# RPI-CM3.net
KiCad netlist of a schematic drawn in Altium Designer
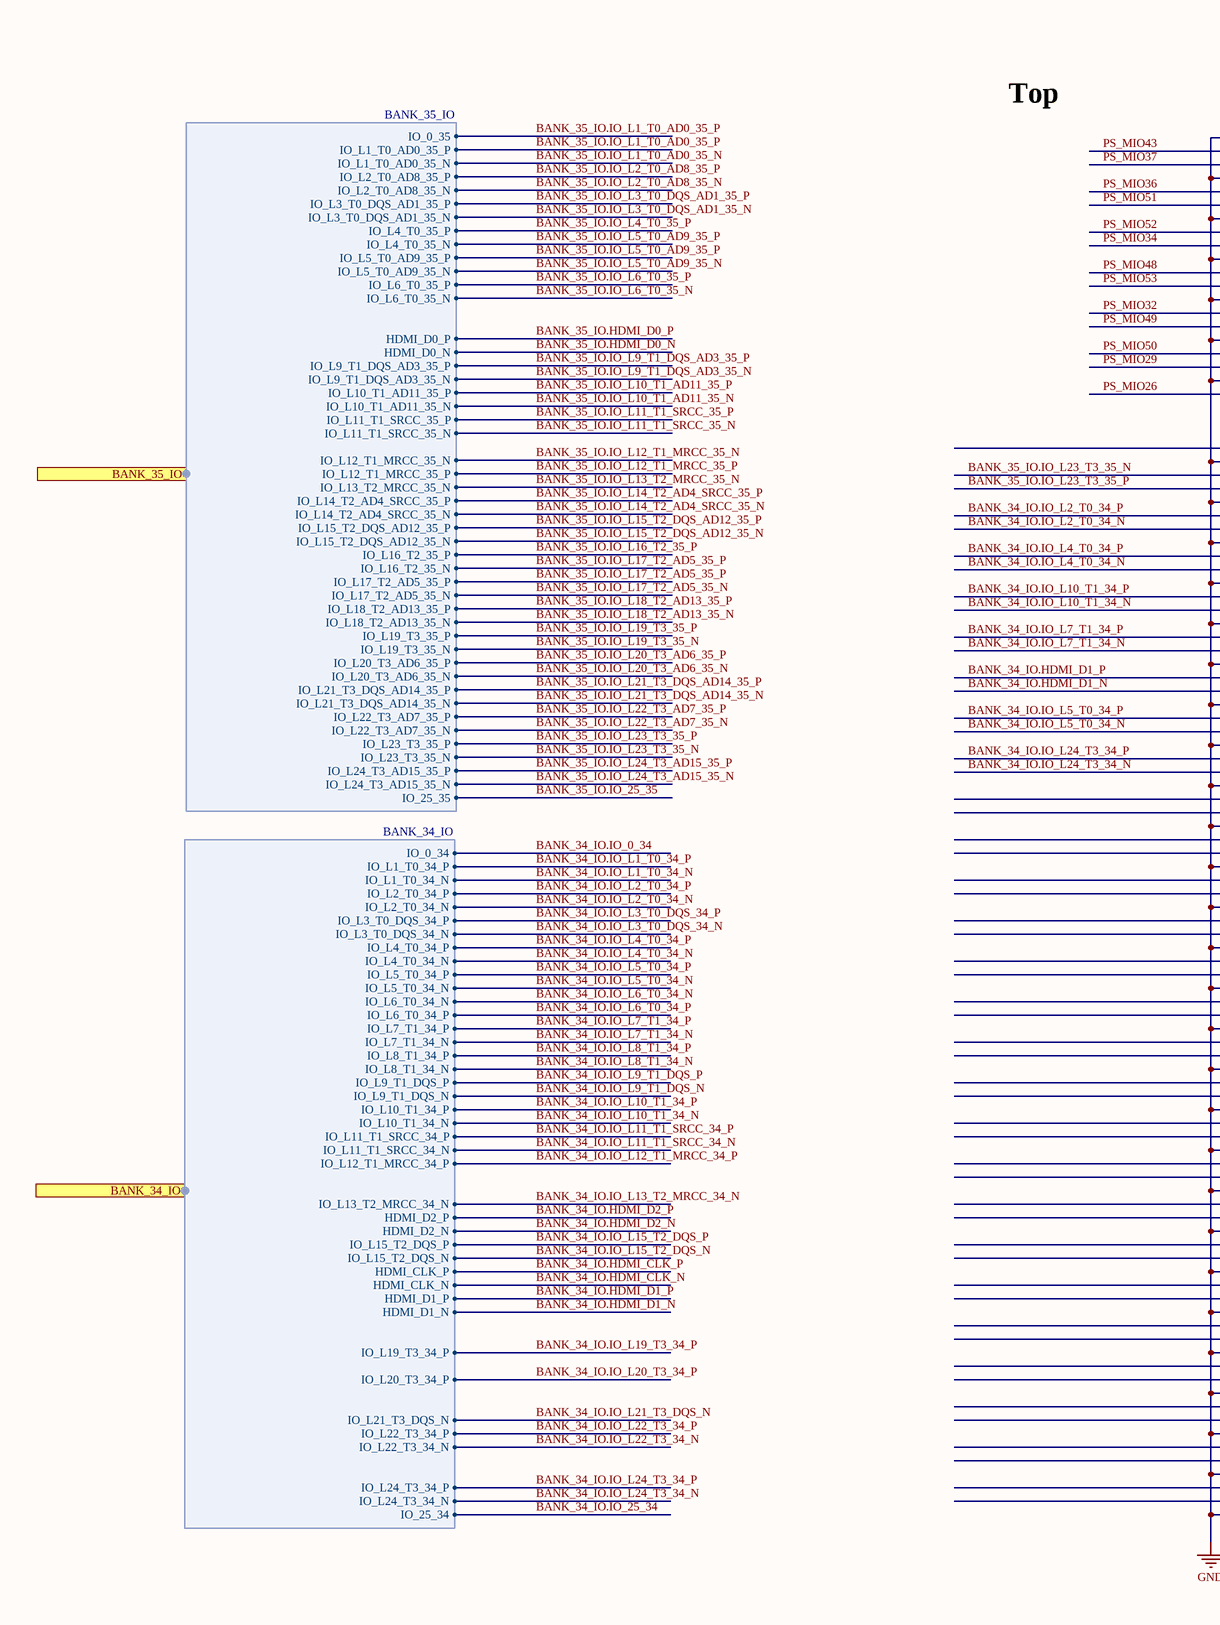
[diagram p0: RPI-CM3.SchDoc, left]
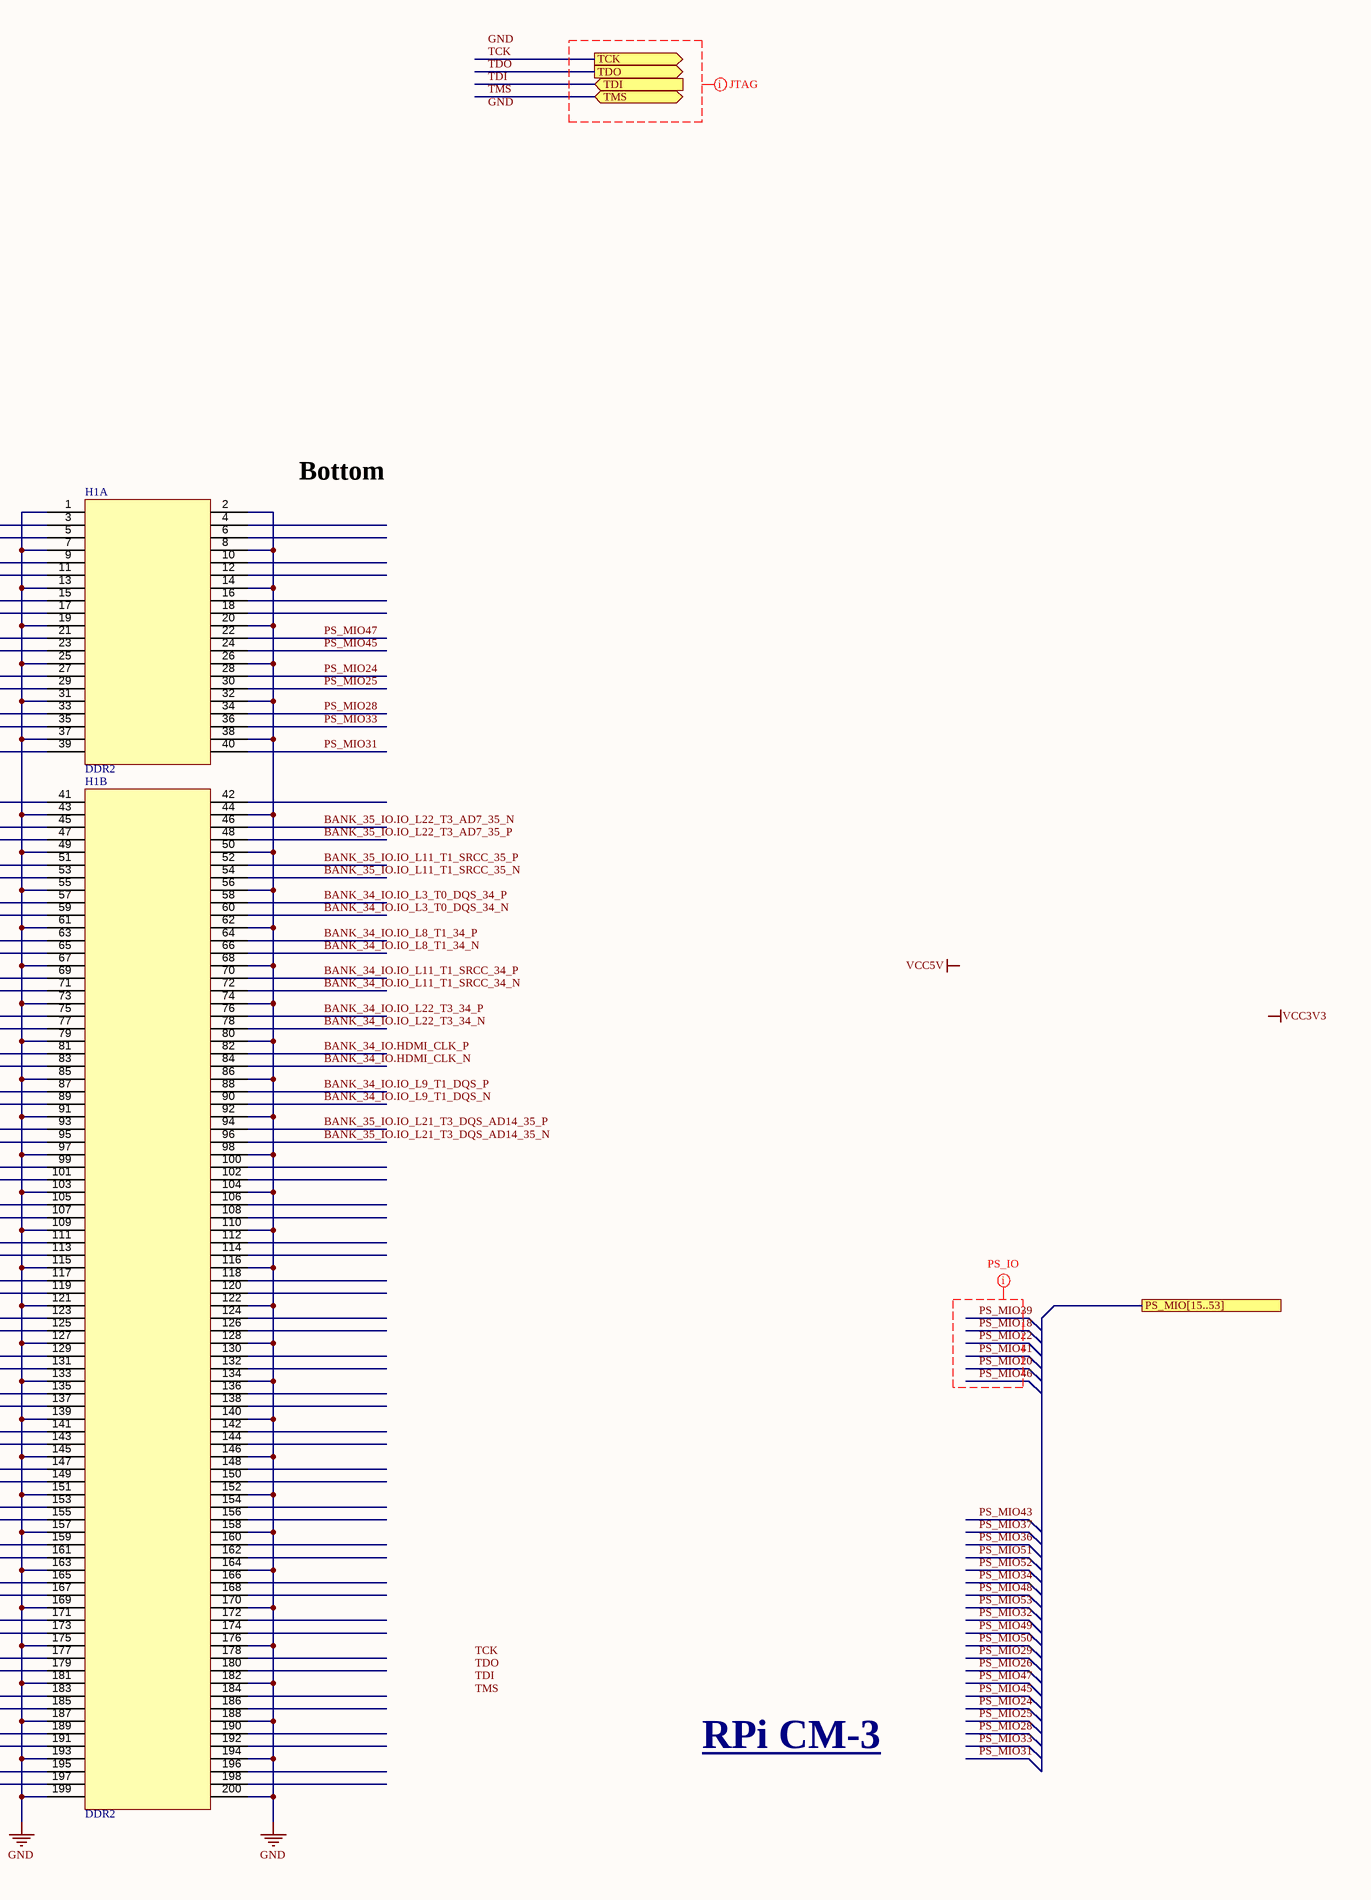
[diagram p1: RPI-CM3.SchDoc, right]

(export (version "E")
  (design (tool "Eeschema 10.0.6"))
  (components
    (comp (ref "H1")
      (value "DDR2")
      (footprint "DDR2-SO-DIMM")
      (libsource (lib "CCZynq") (part "DDR2_SODIMM"))
    )
  )
  (nets
    (net (code "16") (name "/BANK_34_IO.HDMI_CLK_N") (class "Default")
      (node (ref "H1") (pin "84") (pintype "passive"))
    )
    (net (code "17") (name "/BANK_34_IO.HDMI_CLK_P") (class "Default")
      (node (ref "H1") (pin "82") (pintype "passive"))
    )
    (net (code "18") (name "/BANK_34_IO.HDMI_D1_N") (class "Default")
      (node (ref "H1") (pin "77") (pintype "passive"))
    )
    (net (code "19") (name "/BANK_34_IO.HDMI_D1_P") (class "Default")
      (node (ref "H1") (pin "75") (pintype "passive"))
    )
    (net (code "26") (name "/BANK_34_IO.IO_L2_T0_34_N") (class "Default")
      (node (ref "H1") (pin "53") (pintype "passive"))
    )
    (net (code "27") (name "/BANK_34_IO.IO_L2_T0_34_P") (class "Default")
      (node (ref "H1") (pin "51") (pintype "passive"))
    )
    (net (code "28") (name "/BANK_34_IO.IO_L3_T0_DQS_34_N") (class "Default")
      (node (ref "H1") (pin "60") (pintype "passive"))
    )
    (net (code "29") (name "/BANK_34_IO.IO_L3_T0_DQS_34_P") (class "Default")
      (node (ref "H1") (pin "58") (pintype "passive"))
    )
    (net (code "30") (name "/BANK_34_IO.IO_L4_T0_34_N") (class "Default")
      (node (ref "H1") (pin "59") (pintype "passive"))
    )
    (net (code "31") (name "/BANK_34_IO.IO_L4_T0_34_P") (class "Default")
      (node (ref "H1") (pin "57") (pintype "passive"))
    )
    (net (code "32") (name "/BANK_34_IO.IO_L5_T0_34_N") (class "Default")
      (node (ref "H1") (pin "83") (pintype "passive"))
    )
    (net (code "33") (name "/BANK_34_IO.IO_L5_T0_34_P") (class "Default")
      (node (ref "H1") (pin "81") (pintype "passive"))
    )
    (net (code "36") (name "/BANK_34_IO.IO_L7_T1_34_N") (class "Default")
      (node (ref "H1") (pin "71") (pintype "passive"))
    )
    (net (code "37") (name "/BANK_34_IO.IO_L7_T1_34_P") (class "Default")
      (node (ref "H1") (pin "69") (pintype "passive"))
    )
    (net (code "38") (name "/BANK_34_IO.IO_L8_T1_34_N") (class "Default")
      (node (ref "H1") (pin "66") (pintype "passive"))
    )
    (net (code "39") (name "/BANK_34_IO.IO_L8_T1_34_P") (class "Default")
      (node (ref "H1") (pin "64") (pintype "passive"))
    )
    (net (code "40") (name "/BANK_34_IO.IO_L9_T1_DQS_N") (class "Default")
      (node (ref "H1") (pin "90") (pintype "passive"))
    )
    (net (code "41") (name "/BANK_34_IO.IO_L9_T1_DQS_P") (class "Default")
      (node (ref "H1") (pin "88") (pintype "passive"))
    )
    (net (code "42") (name "/BANK_34_IO.IO_L10_T1_34_N") (class "Default")
      (node (ref "H1") (pin "65") (pintype "passive"))
    )
    (net (code "43") (name "/BANK_34_IO.IO_L10_T1_34_P") (class "Default")
      (node (ref "H1") (pin "63") (pintype "passive"))
    )
    (net (code "44") (name "/BANK_34_IO.IO_L11_T1_SRCC_34_N") (class "Default")
      (node (ref "H1") (pin "72") (pintype "passive"))
    )
    (net (code "45") (name "/BANK_34_IO.IO_L11_T1_SRCC_34_P") (class "Default")
      (node (ref "H1") (pin "70") (pintype "passive"))
    )
    (net (code "53") (name "/BANK_34_IO.IO_L22_T3_34_N") (class "Default")
      (node (ref "H1") (pin "78") (pintype "passive"))
    )
    (net (code "54") (name "/BANK_34_IO.IO_L22_T3_34_P") (class "Default")
      (node (ref "H1") (pin "76") (pintype "passive"))
    )
    (net (code "55") (name "/BANK_34_IO.IO_L24_T3_34_N") (class "Default")
      (node (ref "H1") (pin "89") (pintype "passive"))
    )
    (net (code "56") (name "/BANK_34_IO.IO_L24_T3_34_P") (class "Default")
      (node (ref "H1") (pin "87") (pintype "passive"))
    )
    (net (code "75") (name "/BANK_35_IO.IO_L11_T1_SRCC_35_N") (class "Default")
      (node (ref "H1") (pin "54") (pintype "passive"))
    )
    (net (code "76") (name "/BANK_35_IO.IO_L11_T1_SRCC_35_P") (class "Default")
      (node (ref "H1") (pin "52") (pintype "passive"))
    )
    (net (code "93") (name "/BANK_35_IO.IO_L21_T3_DQS_AD14_35_N") (class "Default")
      (node (ref "H1") (pin "96") (pintype "passive"))
    )
    (net (code "94") (name "/BANK_35_IO.IO_L21_T3_DQS_AD14_35_P") (class "Default")
      (node (ref "H1") (pin "94") (pintype "passive"))
    )
    (net (code "95") (name "/BANK_35_IO.IO_L22_T3_AD7_35_N") (class "Default")
      (node (ref "H1") (pin "46") (pintype "passive"))
    )
    (net (code "96") (name "/BANK_35_IO.IO_L22_T3_AD7_35_P") (class "Default")
      (node (ref "H1") (pin "48") (pintype "passive"))
    )
    (net (code "97") (name "/BANK_35_IO.IO_L23_T3_35_N") (class "Default")
      (node (ref "H1") (pin "45") (pintype "passive"))
    )
    (net (code "98") (name "/BANK_35_IO.IO_L23_T3_35_P") (class "Default")
      (node (ref "H1") (pin "47") (pintype "passive"))
    )
    (net (code "104") (name "/PS_MIO24") (class "Default") (node (ref "H1") (pin "28") (pintype "passive")))
    (net (code "105") (name "/PS_MIO25") (class "Default") (node (ref "H1") (pin "30") (pintype "passive")))
    (net (code "106") (name "/PS_MIO26") (class "Default") (node (ref "H1") (pin "39") (pintype "passive")))
    (net (code "107") (name "/PS_MIO28") (class "Default") (node (ref "H1") (pin "34") (pintype "passive")))
    (net (code "108") (name "/PS_MIO29") (class "Default") (node (ref "H1") (pin "35") (pintype "passive")))
    (net (code "109") (name "/PS_MIO31") (class "Default") (node (ref "H1") (pin "40") (pintype "passive")))
    (net (code "110") (name "/PS_MIO32") (class "Default") (node (ref "H1") (pin "27") (pintype "passive")))
    (net (code "111") (name "/PS_MIO33") (class "Default") (node (ref "H1") (pin "36") (pintype "passive")))
    (net (code "112") (name "/PS_MIO34") (class "Default") (node (ref "H1") (pin "17") (pintype "passive")))
    (net (code "113") (name "/PS_MIO36") (class "Default") (node (ref "H1") (pin "9") (pintype "passive")))
    (net (code "114") (name "/PS_MIO37") (class "Default") (node (ref "H1") (pin "5") (pintype "passive")))
    (net (code "117") (name "/PS_MIO43") (class "Default") (node (ref "H1") (pin "3") (pintype "passive")))
    (net (code "118") (name "/PS_MIO45") (class "Default") (node (ref "H1") (pin "24") (pintype "passive")))
    (net (code "120") (name "/PS_MIO47") (class "Default") (node (ref "H1") (pin "22") (pintype "passive")))
    (net (code "121") (name "/PS_MIO48") (class "Default") (node (ref "H1") (pin "21") (pintype "passive")))
    (net (code "122") (name "/PS_MIO49") (class "Default") (node (ref "H1") (pin "29") (pintype "passive")))
    (net (code "123") (name "/PS_MIO50") (class "Default") (node (ref "H1") (pin "33") (pintype "passive")))
    (net (code "124") (name "/PS_MIO51") (class "Default") (node (ref "H1") (pin "11") (pintype "passive")))
    (net (code "125") (name "/PS_MIO52") (class "Default") (node (ref "H1") (pin "15") (pintype "passive")))
    (net (code "126") (name "/PS_MIO53") (class "Default") (node (ref "H1") (pin "23") (pintype "passive")))
    (net (code "134") (name "GND") (class "Default")
      (node (ref "H1") (pin "1") (pintype "passive"))
      (node (ref "H1") (pin "103") (pintype "passive"))
      (node (ref "H1") (pin "104") (pintype "passive"))
      (node (ref "H1") (pin "109") (pintype "passive"))
      (node (ref "H1") (pin "110") (pintype "passive"))
      (node (ref "H1") (pin "115") (pintype "passive"))
      (node (ref "H1") (pin "116") (pintype "passive"))
      (node (ref "H1") (pin "121") (pintype "passive"))
      (node (ref "H1") (pin "122") (pintype "passive"))
      (node (ref "H1") (pin "127") (pintype "passive"))
      (node (ref "H1") (pin "128") (pintype "passive"))
      (node (ref "H1") (pin "13") (pintype "passive"))
      (node (ref "H1") (pin "133") (pintype "passive"))
      (node (ref "H1") (pin "134") (pintype "passive"))
      (node (ref "H1") (pin "139") (pintype "passive"))
      (node (ref "H1") (pin "14") (pintype "passive"))
      (node (ref "H1") (pin "140") (pintype "passive"))
      (node (ref "H1") (pin "145") (pintype "passive"))
      (node (ref "H1") (pin "146") (pintype "passive"))
      (node (ref "H1") (pin "151") (pintype "passive"))
      (node (ref "H1") (pin "152") (pintype "passive"))
      (node (ref "H1") (pin "157") (pintype "passive"))
      (node (ref "H1") (pin "158") (pintype "passive"))
      (node (ref "H1") (pin "163") (pintype "passive"))
      (node (ref "H1") (pin "164") (pintype "passive"))
      (node (ref "H1") (pin "169") (pintype "passive"))
      (node (ref "H1") (pin "170") (pintype "passive"))
      (node (ref "H1") (pin "175") (pintype "passive"))
      (node (ref "H1") (pin "176") (pintype "passive"))
      (node (ref "H1") (pin "181") (pintype "passive"))
      (node (ref "H1") (pin "182") (pintype "passive"))
      (node (ref "H1") (pin "187") (pintype "passive"))
      (node (ref "H1") (pin "188") (pintype "passive"))
      (node (ref "H1") (pin "19") (pintype "passive"))
      (node (ref "H1") (pin "193") (pintype "passive"))
      (node (ref "H1") (pin "194") (pintype "passive"))
      (node (ref "H1") (pin "199") (pintype "passive"))
      (node (ref "H1") (pin "2") (pintype "passive"))
      (node (ref "H1") (pin "20") (pintype "passive"))
      (node (ref "H1") (pin "200") (pintype "passive"))
      (node (ref "H1") (pin "25") (pintype "passive"))
      (node (ref "H1") (pin "26") (pintype "passive"))
      (node (ref "H1") (pin "31") (pintype "passive"))
      (node (ref "H1") (pin "32") (pintype "passive"))
      (node (ref "H1") (pin "37") (pintype "passive"))
      (node (ref "H1") (pin "38") (pintype "passive"))
      (node (ref "H1") (pin "43") (pintype "passive"))
      (node (ref "H1") (pin "44") (pintype "passive"))
      (node (ref "H1") (pin "49") (pintype "passive"))
      (node (ref "H1") (pin "50") (pintype "passive"))
      (node (ref "H1") (pin "55") (pintype "passive"))
      (node (ref "H1") (pin "56") (pintype "passive"))
      (node (ref "H1") (pin "61") (pintype "passive"))
      (node (ref "H1") (pin "62") (pintype "passive"))
      (node (ref "H1") (pin "67") (pintype "passive"))
      (node (ref "H1") (pin "68") (pintype "passive"))
      (node (ref "H1") (pin "7") (pintype "passive"))
      (node (ref "H1") (pin "73") (pintype "passive"))
      (node (ref "H1") (pin "74") (pintype "passive"))
      (node (ref "H1") (pin "79") (pintype "passive"))
      (node (ref "H1") (pin "8") (pintype "passive"))
      (node (ref "H1") (pin "80") (pintype "passive"))
      (node (ref "H1") (pin "85") (pintype "passive"))
      (node (ref "H1") (pin "86") (pintype "passive"))
      (node (ref "H1") (pin "91") (pintype "passive"))
      (node (ref "H1") (pin "92") (pintype "passive"))
      (node (ref "H1") (pin "97") (pintype "passive"))
      (node (ref "H1") (pin "98") (pintype "passive"))
    )
    (net (code "137") (name "unconnected-(H1-Pad4)") (class "Default")
      (node (ref "H1") (pin "4") (pintype "passive"))
    )
    (net (code "138") (name "unconnected-(H1-Pad6)") (class "Default")
      (node (ref "H1") (pin "6") (pintype "passive"))
    )
    (net (code "139") (name "unconnected-(H1-Pad10)") (class "Default")
      (node (ref "H1") (pin "10") (pintype "passive"))
    )
    (net (code "140") (name "unconnected-(H1-Pad12)") (class "Default")
      (node (ref "H1") (pin "12") (pintype "passive"))
    )
    (net (code "141") (name "unconnected-(H1-Pad16)") (class "Default")
      (node (ref "H1") (pin "16") (pintype "passive"))
    )
    (net (code "142") (name "unconnected-(H1-Pad18)") (class "Default")
      (node (ref "H1") (pin "18") (pintype "passive"))
    )
    (net (code "143") (name "unconnected-(H1-Pad41)") (class "Default")
      (node (ref "H1") (pin "41") (pintype "passive"))
    )
    (net (code "144") (name "unconnected-(H1-Pad42)") (class "Default")
      (node (ref "H1") (pin "42") (pintype "passive"))
    )
    (net (code "145") (name "unconnected-(H1-Pad93)") (class "Default")
      (node (ref "H1") (pin "93") (pintype "passive"))
    )
    (net (code "146") (name "unconnected-(H1-Pad95)") (class "Default")
      (node (ref "H1") (pin "95") (pintype "passive"))
    )
    (net (code "147") (name "unconnected-(H1-Pad99)") (class "Default")
      (node (ref "H1") (pin "99") (pintype "passive"))
    )
    (net (code "148") (name "unconnected-(H1-Pad100)") (class "Default")
      (node (ref "H1") (pin "100") (pintype "passive"))
    )
    (net (code "149") (name "unconnected-(H1-Pad101)") (class "Default")
      (node (ref "H1") (pin "101") (pintype "passive"))
    )
    (net (code "150") (name "unconnected-(H1-Pad102)") (class "Default")
      (node (ref "H1") (pin "102") (pintype "passive"))
    )
    (net (code "151") (name "unconnected-(H1-Pad105)") (class "Default")
      (node (ref "H1") (pin "105") (pintype "passive"))
    )
    (net (code "152") (name "unconnected-(H1-Pad106)") (class "Default")
      (node (ref "H1") (pin "106") (pintype "passive"))
    )
    (net (code "153") (name "unconnected-(H1-Pad107)") (class "Default")
      (node (ref "H1") (pin "107") (pintype "passive"))
    )
    (net (code "154") (name "unconnected-(H1-Pad108)") (class "Default")
      (node (ref "H1") (pin "108") (pintype "passive"))
    )
    (net (code "155") (name "unconnected-(H1-Pad111)") (class "Default")
      (node (ref "H1") (pin "111") (pintype "passive"))
    )
    (net (code "156") (name "unconnected-(H1-Pad112)") (class "Default")
      (node (ref "H1") (pin "112") (pintype "passive"))
    )
    (net (code "157") (name "unconnected-(H1-Pad113)") (class "Default")
      (node (ref "H1") (pin "113") (pintype "passive"))
    )
    (net (code "158") (name "unconnected-(H1-Pad114)") (class "Default")
      (node (ref "H1") (pin "114") (pintype "passive"))
    )
    (net (code "159") (name "unconnected-(H1-Pad117)") (class "Default")
      (node (ref "H1") (pin "117") (pintype "passive"))
    )
    (net (code "160") (name "unconnected-(H1-Pad118)") (class "Default")
      (node (ref "H1") (pin "118") (pintype "passive"))
    )
    (net (code "161") (name "unconnected-(H1-Pad119)") (class "Default")
      (node (ref "H1") (pin "119") (pintype "passive"))
    )
    (net (code "162") (name "unconnected-(H1-Pad120)") (class "Default")
      (node (ref "H1") (pin "120") (pintype "passive"))
    )
    (net (code "163") (name "unconnected-(H1-Pad123)") (class "Default")
      (node (ref "H1") (pin "123") (pintype "passive"))
    )
    (net (code "164") (name "unconnected-(H1-Pad124)") (class "Default")
      (node (ref "H1") (pin "124") (pintype "passive"))
    )
    (net (code "165") (name "unconnected-(H1-Pad125)") (class "Default")
      (node (ref "H1") (pin "125") (pintype "passive"))
    )
    (net (code "166") (name "unconnected-(H1-Pad126)") (class "Default")
      (node (ref "H1") (pin "126") (pintype "passive"))
    )
    (net (code "167") (name "unconnected-(H1-Pad129)") (class "Default")
      (node (ref "H1") (pin "129") (pintype "passive"))
    )
    (net (code "168") (name "unconnected-(H1-Pad130)") (class "Default")
      (node (ref "H1") (pin "130") (pintype "passive"))
    )
    (net (code "169") (name "unconnected-(H1-Pad131)") (class "Default")
      (node (ref "H1") (pin "131") (pintype "passive"))
    )
    (net (code "170") (name "unconnected-(H1-Pad132)") (class "Default")
      (node (ref "H1") (pin "132") (pintype "passive"))
    )
    (net (code "171") (name "unconnected-(H1-Pad135)") (class "Default")
      (node (ref "H1") (pin "135") (pintype "passive"))
    )
    (net (code "172") (name "unconnected-(H1-Pad136)") (class "Default")
      (node (ref "H1") (pin "136") (pintype "passive"))
    )
    (net (code "173") (name "unconnected-(H1-Pad137)") (class "Default")
      (node (ref "H1") (pin "137") (pintype "passive"))
    )
    (net (code "174") (name "unconnected-(H1-Pad138)") (class "Default")
      (node (ref "H1") (pin "138") (pintype "passive"))
    )
    (net (code "175") (name "unconnected-(H1-Pad141)") (class "Default")
      (node (ref "H1") (pin "141") (pintype "passive"))
    )
    (net (code "176") (name "unconnected-(H1-Pad142)") (class "Default")
      (node (ref "H1") (pin "142") (pintype "passive"))
    )
    (net (code "177") (name "unconnected-(H1-Pad143)") (class "Default")
      (node (ref "H1") (pin "143") (pintype "passive"))
    )
    (net (code "178") (name "unconnected-(H1-Pad144)") (class "Default")
      (node (ref "H1") (pin "144") (pintype "passive"))
    )
    (net (code "179") (name "unconnected-(H1-Pad147)") (class "Default")
      (node (ref "H1") (pin "147") (pintype "passive"))
    )
    (net (code "180") (name "unconnected-(H1-Pad148)") (class "Default")
      (node (ref "H1") (pin "148") (pintype "passive"))
    )
    (net (code "181") (name "unconnected-(H1-Pad149)") (class "Default")
      (node (ref "H1") (pin "149") (pintype "passive"))
    )
    (net (code "182") (name "unconnected-(H1-Pad150)") (class "Default")
      (node (ref "H1") (pin "150") (pintype "passive"))
    )
    (net (code "183") (name "unconnected-(H1-Pad153)") (class "Default")
      (node (ref "H1") (pin "153") (pintype "passive"))
    )
    (net (code "184") (name "unconnected-(H1-Pad154)") (class "Default")
      (node (ref "H1") (pin "154") (pintype "passive"))
    )
    (net (code "185") (name "unconnected-(H1-Pad155)") (class "Default")
      (node (ref "H1") (pin "155") (pintype "passive"))
    )
    (net (code "186") (name "unconnected-(H1-Pad156)") (class "Default")
      (node (ref "H1") (pin "156") (pintype "passive"))
    )
    (net (code "187") (name "unconnected-(H1-Pad159)") (class "Default")
      (node (ref "H1") (pin "159") (pintype "passive"))
    )
    (net (code "188") (name "unconnected-(H1-Pad160)") (class "Default")
      (node (ref "H1") (pin "160") (pintype "passive"))
    )
    (net (code "189") (name "unconnected-(H1-Pad161)") (class "Default")
      (node (ref "H1") (pin "161") (pintype "passive"))
    )
    (net (code "190") (name "unconnected-(H1-Pad162)") (class "Default")
      (node (ref "H1") (pin "162") (pintype "passive"))
    )
    (net (code "191") (name "unconnected-(H1-Pad165)") (class "Default")
      (node (ref "H1") (pin "165") (pintype "passive"))
    )
    (net (code "192") (name "unconnected-(H1-Pad166)") (class "Default")
      (node (ref "H1") (pin "166") (pintype "passive"))
    )
    (net (code "193") (name "unconnected-(H1-Pad167)") (class "Default")
      (node (ref "H1") (pin "167") (pintype "passive"))
    )
    (net (code "194") (name "unconnected-(H1-Pad168)") (class "Default")
      (node (ref "H1") (pin "168") (pintype "passive"))
    )
    (net (code "195") (name "unconnected-(H1-Pad171)") (class "Default")
      (node (ref "H1") (pin "171") (pintype "passive"))
    )
    (net (code "196") (name "unconnected-(H1-Pad172)") (class "Default")
      (node (ref "H1") (pin "172") (pintype "passive"))
    )
    (net (code "197") (name "unconnected-(H1-Pad173)") (class "Default")
      (node (ref "H1") (pin "173") (pintype "passive"))
    )
    (net (code "198") (name "unconnected-(H1-Pad174)") (class "Default")
      (node (ref "H1") (pin "174") (pintype "passive"))
    )
    (net (code "199") (name "unconnected-(H1-Pad177)") (class "Default")
      (node (ref "H1") (pin "177") (pintype "passive"))
    )
    (net (code "200") (name "unconnected-(H1-Pad178)") (class "Default")
      (node (ref "H1") (pin "178") (pintype "passive"))
    )
    (net (code "201") (name "unconnected-(H1-Pad179)") (class "Default")
      (node (ref "H1") (pin "179") (pintype "passive"))
    )
    (net (code "202") (name "unconnected-(H1-Pad180)") (class "Default")
      (node (ref "H1") (pin "180") (pintype "passive"))
    )
    (net (code "203") (name "unconnected-(H1-Pad183)") (class "Default")
      (node (ref "H1") (pin "183") (pintype "passive"))
    )
    (net (code "204") (name "unconnected-(H1-Pad184)") (class "Default")
      (node (ref "H1") (pin "184") (pintype "passive"))
    )
    (net (code "205") (name "unconnected-(H1-Pad185)") (class "Default")
      (node (ref "H1") (pin "185") (pintype "passive"))
    )
    (net (code "206") (name "unconnected-(H1-Pad186)") (class "Default")
      (node (ref "H1") (pin "186") (pintype "passive"))
    )
    (net (code "207") (name "unconnected-(H1-Pad189)") (class "Default")
      (node (ref "H1") (pin "189") (pintype "passive"))
    )
    (net (code "208") (name "unconnected-(H1-Pad190)") (class "Default")
      (node (ref "H1") (pin "190") (pintype "passive"))
    )
    (net (code "209") (name "unconnected-(H1-Pad191)") (class "Default")
      (node (ref "H1") (pin "191") (pintype "passive"))
    )
    (net (code "210") (name "unconnected-(H1-Pad192)") (class "Default")
      (node (ref "H1") (pin "192") (pintype "passive"))
    )
    (net (code "211") (name "unconnected-(H1-Pad195)") (class "Default")
      (node (ref "H1") (pin "195") (pintype "passive"))
    )
    (net (code "212") (name "unconnected-(H1-Pad196)") (class "Default")
      (node (ref "H1") (pin "196") (pintype "passive"))
    )
    (net (code "213") (name "unconnected-(H1-Pad197)") (class "Default")
      (node (ref "H1") (pin "197") (pintype "passive"))
    )
    (net (code "214") (name "unconnected-(H1-Pad198)") (class "Default")
      (node (ref "H1") (pin "198") (pintype "passive"))
    )
  )
)
